# poweramp.net
KiCad netlist of a schematic drawn in Altium Designer
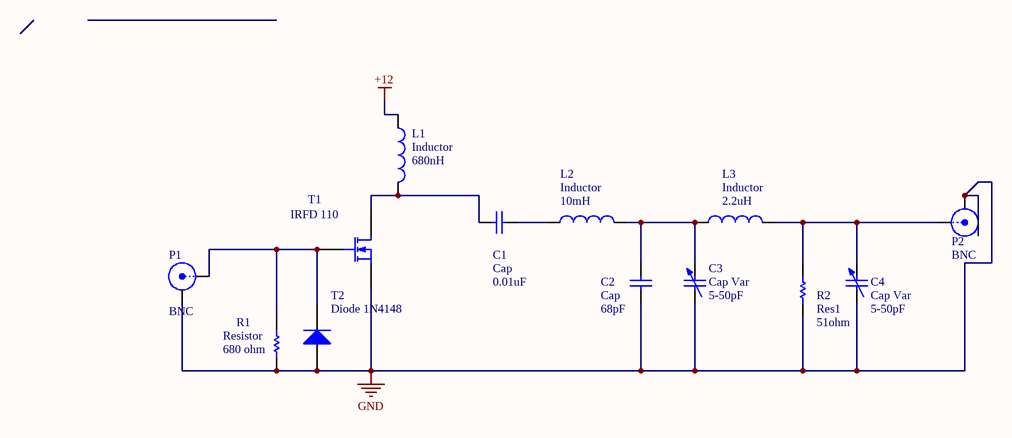
[diagram p0: poweramp.SchDoc]

(export (version "E")
  (design (tool "Eeschema 10.0.6"))
  (components
    (comp (ref "C1")
      (value "Cap")
      (footprint "RAD-0.3")
      (description "Capacitor")
      (fields (field (name "ALTIUM_VALUE") "0.01uF") (field (name "PUBLISHER") "Altium Limited"))
      (libsource (lib "Miscellaneous Devices") (part "Cap"))
    )
    (comp (ref "C2")
      (value "Cap")
      (footprint "RAD-0.3")
      (description "Capacitor")
      (fields (field (name "ALTIUM_VALUE") "68pF") (field (name "PUBLISHER") "Altium Limited"))
      (libsource (lib "Miscellaneous Devices") (part "Cap"))
    )
    (comp (ref "C3")
      (value "Cap Var")
      (footprint "C1210_N")
      (description "Variable or Adjustable Capacitor")
      (fields (field (name "ALTIUM_VALUE") "5-50pF") (field (name "PUBLISHER") "Altium Limited"))
      (libsource (lib "Miscellaneous Devices") (part "Cap Var"))
    )
    (comp (ref "C4")
      (value "Cap Var")
      (footprint "C1210_N")
      (description "Variable or Adjustable Capacitor")
      (fields (field (name "ALTIUM_VALUE") "5-50pF") (field (name "PUBLISHER") "Altium Limited"))
      (libsource (lib "Miscellaneous Devices") (part "Cap Var"))
    )
    (comp (ref "L1")
      (value "Inductor")
      (footprint "0402-A")
      (fields (field (name "ALTIUM_VALUE") "680nH") (field (name "PUBLISHER") "Altium Limited"))
      (libsource (lib "Miscellaneous Devices") (part "Inductor"))
    )
    (comp (ref "L2")
      (value "Inductor")
      (footprint "0402-A")
      (fields (field (name "ALTIUM_VALUE") "10mH") (field (name "PUBLISHER") "Altium Limited"))
      (libsource (lib "Miscellaneous Devices") (part "Inductor"))
    )
    (comp (ref "L3")
      (value "Inductor")
      (footprint "0402-A")
      (fields (field (name "ALTIUM_VALUE") "2.2uH") (field (name "PUBLISHER") "Altium Limited"))
      (libsource (lib "Miscellaneous Devices") (part "Inductor"))
    )
    (comp (ref "P1")
      (value "BNC")
      (footprint "BNC_RA CON")
      (description "BNC Elbow Connector")
      (fields (field (name "PUBLISHER") "Altium Limited"))
      (libsource (lib "poweramp") (part "BNC"))
    )
    (comp (ref "P2")
      (value "BNC")
      (footprint "BNC_RA CON")
      (description "BNC Elbow Connector")
      (fields (field (name "PUBLISHER") "Altium Limited"))
      (libsource (lib "poweramp") (part "BNC"))
    )
    (comp (ref "R1")
      (value "Resistor")
      (footprint "AXIAL-0.3")
      (fields (field (name "ALTIUM_VALUE") "680 ohm") (field (name "PUBLISHER") "Altium Limited"))
      (libsource (lib "Miscellaneous Devices") (part "Res1"))
    )
    (comp (ref "R2")
      (value "Res1")
      (footprint "AXIAL-0.3")
      (description "Resistor")
      (fields (field (name "ALTIUM_VALUE") "51ohm") (field (name "PUBLISHER") "Altium Limited"))
      (libsource (lib "Miscellaneous Devices") (part "Res1"))
    )
    (comp (ref "T1")
      (value "IRFD 110")
      (footprint "E3")
      (description "N-Channel MOSFET")
      (fields (field (name "PUBLISHER") "Altium Limited"))
      (libsource (lib "Miscellaneous Devices") (part "MOSFET-N"))
    )
    (comp (ref "T2")
      (value "Diode 1N4148")
      (footprint "DO-35")
      (description "High Conductance Fast Diode")
      (fields (field (name "PUBLISHER") "Altium Limited"))
      (libsource (lib "Miscellaneous Devices") (part "Diode 1N4148"))
    )
  )
  (nets
    (net (code "1") (name "+12") (class "Default")
      (node (ref "L1") (pin "1") (pinfunction "1_1") (pintype "passive"))
    )
    (net (code "2") (name "GND") (class "Default")
      (node (ref "C2") (pin "1") (pinfunction "1_1") (pintype "passive"))
      (node (ref "C3") (pin "1") (pinfunction "1_1") (pintype "passive"))
      (node (ref "C4") (pin "1") (pinfunction "1_1") (pintype "passive"))
      (node (ref "P1") (pin "2") (pinfunction "Y_2") (pintype "passive"))
      (node (ref "P2") (pin "2") (pinfunction "Y_2") (pintype "passive"))
      (node (ref "R1") (pin "2") (pinfunction "2_2") (pintype "passive"))
      (node (ref "R2") (pin "1") (pinfunction "1_1") (pintype "passive"))
      (node (ref "T1") (pin "3") (pinfunction "S_3") (pintype "passive"))
      (node (ref "T2") (pin "1") (pinfunction "A_1") (pintype "passive"))
    )
    (net (code "3") (name "Net-(C1-Pad2)") (class "Default")
      (node (ref "C1") (pin "2") (pinfunction "2_2") (pintype "passive"))
      (node (ref "L2") (pin "1") (pinfunction "1_1") (pintype "passive"))
    )
    (net (code "4") (name "Net-(C2-Pad2)") (class "Default")
      (node (ref "C2") (pin "2") (pinfunction "2_2") (pintype "passive"))
      (node (ref "C3") (pin "2") (pinfunction "2_2") (pintype "passive"))
      (node (ref "L2") (pin "2") (pinfunction "2_2") (pintype "passive"))
      (node (ref "L3") (pin "1") (pinfunction "1_1") (pintype "passive"))
    )
    (net (code "5") (name "Net-(P1-X)") (class "Default")
      (node (ref "P1") (pin "1") (pinfunction "X_1") (pintype "passive"))
      (node (ref "R1") (pin "1") (pinfunction "1_1") (pintype "passive"))
      (node (ref "T1") (pin "2") (pinfunction "G_2") (pintype "passive"))
      (node (ref "T2") (pin "2") (pinfunction "K_2") (pintype "passive"))
    )
    (net (code "6") (name "Net-(P2-X)") (class "Default")
      (node (ref "C4") (pin "2") (pinfunction "2_2") (pintype "passive"))
      (node (ref "L3") (pin "2") (pinfunction "2_2") (pintype "passive"))
      (node (ref "P2") (pin "1") (pinfunction "X_1") (pintype "passive"))
      (node (ref "R2") (pin "2") (pinfunction "2_2") (pintype "passive"))
    )
    (net (code "7") (name "Net-(T1-D)") (class "Default")
      (node (ref "C1") (pin "1") (pinfunction "1_1") (pintype "passive"))
      (node (ref "L1") (pin "2") (pinfunction "2_2") (pintype "passive"))
      (node (ref "T1") (pin "1") (pinfunction "D_1") (pintype "passive"))
    )
  )
)
